# shema.net
KiCad netlist of a schematic drawn in EAGLE
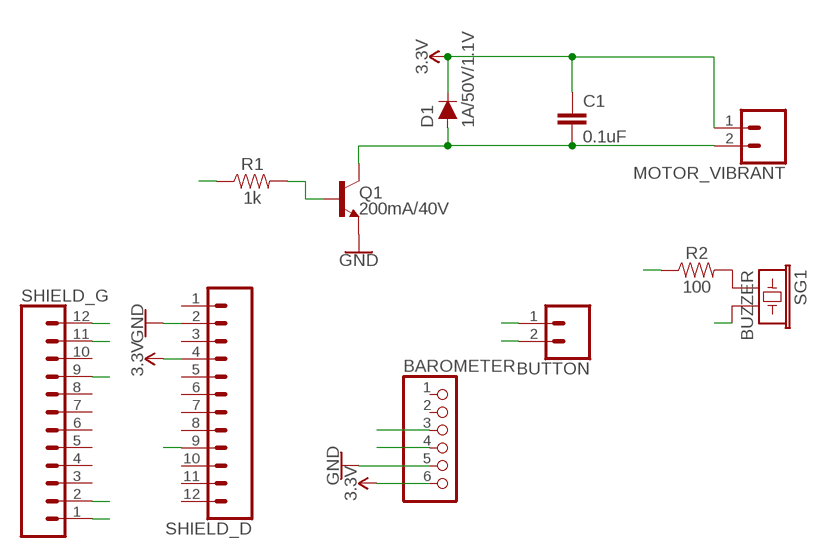
[diagram p0: schematic, sheet 1]

(export (version "E")
  (design (tool "Eeschema 10.0.6"))
  (components
    (comp (ref "BAROMETER")
      (value "PINHD-1X6")
      (footprint "eagle-import:1X06")
      (libsource (lib "eagle-import") (part "PINHD-1X6"))
    )
    (comp (ref "BUTTON")
      (value "CONN_02")
      (footprint "eagle-import:1X02")
      (libsource (lib "eagle-import") (part "SparkFun-Retired_CONN_02"))
    )
    (comp (ref "C1")
      (value "0.1uF")
      (footprint "eagle-import:CAP-PTH-SMALL-KIT")
      (libsource (lib "eagle-import") (part "0.1UF-KIT-EZ-50V-20%"))
    )
    (comp (ref "D1")
      (value "1A/50V/1.1V")
      (footprint "eagle-import:DIODE-1N4001")
      (libsource (lib "eagle-import") (part "DIODE-PTH"))
    )
    (comp (ref "MOTOR_VIBRANT")
      (value "CONN_02")
      (footprint "eagle-import:1X02")
      (libsource (lib "eagle-import") (part "CONN_02"))
    )
    (comp (ref "Q1")
      (value "200mA/40V")
      (footprint "eagle-import:TO-92")
      (libsource (lib "eagle-import") (part "TRANS_NPN-2N3904"))
    )
    (comp (ref "R1")
      (value "1k")
      (footprint "eagle-import:AXIAL-0.3")
      (libsource (lib "eagle-import") (part "1KOHM-HORIZ-1/4W-5%"))
    )
    (comp (ref "R2")
      (value "100")
      (footprint "eagle-import:AXIAL-0.3EZ")
      (libsource (lib "eagle-import") (part "100OHM-HORIZ_KIT-1/4W-1%"))
    )
    (comp (ref "SG1")
      (value "BUZZER")
      (footprint "eagle-import:PS1240P02BT")
      (libsource (lib "eagle-import") (part "BUZZER"))
    )
    (comp (ref "SHIELD_D")
      (value "CONN_12")
      (footprint "eagle-import:1X12")
      (libsource (lib "eagle-import") (part "CONN_12"))
    )
    (comp (ref "SHIELD_G")
      (value "CONN_12")
      (footprint "eagle-import:1X12")
      (libsource (lib "eagle-import") (part "CONN_12"))
    )
  )
  (nets
    (net (code "1") (name "/AUDIO0") (class "Default")
      (node (ref "SG1") (pin "P$2") (pinfunction "2_P$2") (pintype "passive"))
      (node (ref "SHIELD_G") (pin "12") (pinfunction "12_12") (pintype "passive"))
    )
    (net (code "2") (name "/AUDIO1") (class "Default")
      (node (ref "R2") (pin "P$1") (pinfunction "1_P$1") (pintype "passive"))
      (node (ref "SHIELD_G") (pin "11") (pinfunction "11_11") (pintype "passive"))
    )
    (net (code "3") (name "/BUTTON") (class "Default")
      (node (ref "BUTTON") (pin "2") (pinfunction "2_2") (pintype "passive"))
      (node (ref "SHIELD_D") (pin "9") (pinfunction "9_9") (pintype "passive"))
    )
    (net (code "4") (name "/MOTOR_CONTROL") (class "Default")
      (node (ref "R1") (pin "P$1") (pinfunction "1_P$1") (pintype "passive"))
      (node (ref "SHIELD_G") (pin "9") (pinfunction "9_9") (pintype "passive"))
    )
    (net (code "5") (name "/SCL") (class "Default")
      (node (ref "BAROMETER") (pin "4") (pinfunction "4_4") (pintype "passive"))
      (node (ref "SHIELD_G") (pin "1") (pinfunction "1_1") (pintype "passive"))
    )
    (net (code "6") (name "/SDA") (class "Default")
      (node (ref "BAROMETER") (pin "3") (pinfunction "3_3") (pintype "passive"))
      (node (ref "SHIELD_G") (pin "2") (pinfunction "2_2") (pintype "passive"))
    )
    (net (code "7") (name "3.3V") (class "Default")
      (node (ref "BAROMETER") (pin "6") (pinfunction "6_6") (pintype "passive"))
      (node (ref "C1") (pin "1") (pinfunction "1_1") (pintype "passive"))
      (node (ref "D1") (pin "C") (pinfunction "C_C") (pintype "passive"))
      (node (ref "MOTOR_VIBRANT") (pin "1") (pinfunction "1_1") (pintype "passive"))
      (node (ref "SHIELD_D") (pin "4") (pinfunction "4_4") (pintype "passive"))
    )
    (net (code "8") (name "GND") (class "Default")
      (node (ref "BAROMETER") (pin "5") (pinfunction "5_5") (pintype "passive"))
      (node (ref "BUTTON") (pin "1") (pinfunction "1_1") (pintype "passive"))
      (node (ref "Q1") (pin "1") (pinfunction "E_1") (pintype "passive"))
      (node (ref "SHIELD_D") (pin "2") (pinfunction "2_2") (pintype "passive"))
    )
    (net (code "9") (name "Net-(Q1-B)") (class "Default")
      (node (ref "Q1") (pin "2") (pinfunction "B_2") (pintype "passive"))
      (node (ref "R1") (pin "P$2") (pinfunction "2_P$2") (pintype "passive"))
    )
    (net (code "10") (name "Net-(Q1-C)") (class "Default")
      (node (ref "C1") (pin "2") (pinfunction "2_2") (pintype "passive"))
      (node (ref "D1") (pin "A") (pinfunction "A_A") (pintype "passive"))
      (node (ref "MOTOR_VIBRANT") (pin "2") (pinfunction "2_2") (pintype "passive"))
      (node (ref "Q1") (pin "3") (pinfunction "C_3") (pintype "passive"))
    )
    (net (code "11") (name "Net-(R2-2)") (class "Default")
      (node (ref "R2") (pin "P$2") (pinfunction "2_P$2") (pintype "passive"))
      (node (ref "SG1") (pin "P$1") (pinfunction "1_P$1") (pintype "passive"))
    )
    (net (code "12") (name "unconnected-(BAROMETER-Pad1)") (class "Default")
      (node (ref "BAROMETER") (pin "1") (pinfunction "1_1") (pintype "passive"))
    )
    (net (code "13") (name "unconnected-(BAROMETER-Pad2)") (class "Default")
      (node (ref "BAROMETER") (pin "2") (pinfunction "2_2") (pintype "passive"))
    )
    (net (code "14") (name "unconnected-(SHIELD_D-Pad1)") (class "Default")
      (node (ref "SHIELD_D") (pin "1") (pinfunction "1_1") (pintype "passive"))
    )
    (net (code "15") (name "unconnected-(SHIELD_D-Pad3)") (class "Default")
      (node (ref "SHIELD_D") (pin "3") (pinfunction "3_3") (pintype "passive"))
    )
    (net (code "16") (name "unconnected-(SHIELD_D-Pad5)") (class "Default")
      (node (ref "SHIELD_D") (pin "5") (pinfunction "5_5") (pintype "passive"))
    )
    (net (code "17") (name "unconnected-(SHIELD_D-Pad6)") (class "Default")
      (node (ref "SHIELD_D") (pin "6") (pinfunction "6_6") (pintype "passive"))
    )
    (net (code "18") (name "unconnected-(SHIELD_D-Pad7)") (class "Default")
      (node (ref "SHIELD_D") (pin "7") (pinfunction "7_7") (pintype "passive"))
    )
    (net (code "19") (name "unconnected-(SHIELD_D-Pad8)") (class "Default")
      (node (ref "SHIELD_D") (pin "8") (pinfunction "8_8") (pintype "passive"))
    )
    (net (code "20") (name "unconnected-(SHIELD_D-Pad10)") (class "Default")
      (node (ref "SHIELD_D") (pin "10") (pinfunction "10_10") (pintype "passive"))
    )
    (net (code "21") (name "unconnected-(SHIELD_D-Pad11)") (class "Default")
      (node (ref "SHIELD_D") (pin "11") (pinfunction "11_11") (pintype "passive"))
    )
    (net (code "22") (name "unconnected-(SHIELD_D-Pad12)") (class "Default")
      (node (ref "SHIELD_D") (pin "12") (pinfunction "12_12") (pintype "passive"))
    )
    (net (code "23") (name "unconnected-(SHIELD_G-Pad3)") (class "Default")
      (node (ref "SHIELD_G") (pin "3") (pinfunction "3_3") (pintype "passive"))
    )
    (net (code "24") (name "unconnected-(SHIELD_G-Pad4)") (class "Default")
      (node (ref "SHIELD_G") (pin "4") (pinfunction "4_4") (pintype "passive"))
    )
    (net (code "25") (name "unconnected-(SHIELD_G-Pad5)") (class "Default")
      (node (ref "SHIELD_G") (pin "5") (pinfunction "5_5") (pintype "passive"))
    )
    (net (code "26") (name "unconnected-(SHIELD_G-Pad6)") (class "Default")
      (node (ref "SHIELD_G") (pin "6") (pinfunction "6_6") (pintype "passive"))
    )
    (net (code "27") (name "unconnected-(SHIELD_G-Pad7)") (class "Default")
      (node (ref "SHIELD_G") (pin "7") (pinfunction "7_7") (pintype "passive"))
    )
    (net (code "28") (name "unconnected-(SHIELD_G-Pad8)") (class "Default")
      (node (ref "SHIELD_G") (pin "8") (pinfunction "8_8") (pintype "passive"))
    )
    (net (code "29") (name "unconnected-(SHIELD_G-Pad10)") (class "Default")
      (node (ref "SHIELD_G") (pin "10") (pinfunction "10_10") (pintype "passive"))
    )
  )
)
